# DisplayBoard.net
KiCad netlist of a schematic drawn in EAGLE
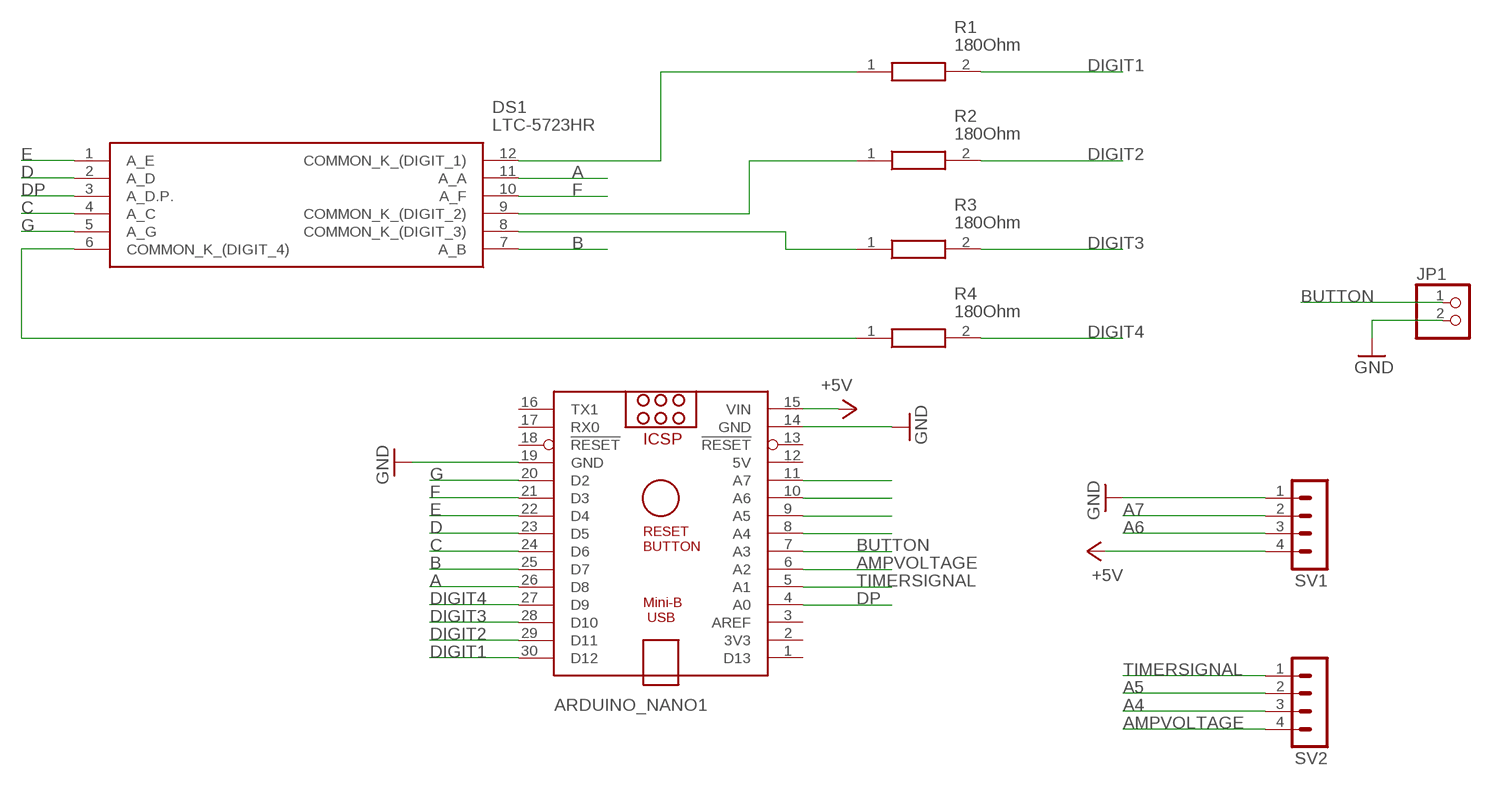
[diagram p0: schematic, sheet 1]

(export (version "E")
  (design (tool "Eeschema 10.0.6"))
  (components
    (comp (ref "ARDUINO_NANO1")
      (value "ARDUINO_NANO")
      (footprint "eagle-import:ARDUINO_NANO")
      (libsource (lib "eagle-import") (part "ARDUINO_NANO"))
    )
    (comp (ref "DS1")
      (value "LTC-5723HR")
      (footprint "eagle-import:DIP1524W75P254L5030H825Q12N")
      (fields (field (name "MOUSER_PART_NUMBER") "859-LTC-5723HR"))
      (libsource (lib "eagle-import") (part "LTC-5723HR"))
    )
    (comp (ref "JP1")
      (value "PINHD-1X2")
      (footprint "eagle-import:1X02")
      (libsource (lib "eagle-import") (part "PINHD-1X2"))
    )
    (comp (ref "R1")
      (value "180Ohm")
      (footprint "eagle-import:RESC2012X60N")
      (fields
        (field (name "MANUFACTURER_PART_NUMBER") "ERA-6AEB181V")
        (field (name "MOUSER_PART_NUMBER") "667-ERA-6AEB181V")
      )
      (libsource (lib "eagle-import") (part "ERA-6AEB181V"))
    )
    (comp (ref "R2")
      (value "180Ohm")
      (footprint "eagle-import:RESC2012X60N")
      (fields
        (field (name "MANUFACTURER_PART_NUMBER") "ERA-6AEB181V")
        (field (name "MOUSER_PART_NUMBER") "667-ERA-6AEB181V")
      )
      (libsource (lib "eagle-import") (part "ERA-6AEB181V"))
    )
    (comp (ref "R3")
      (value "180Ohm")
      (footprint "eagle-import:RESC2012X60N")
      (fields
        (field (name "MANUFACTURER_PART_NUMBER") "ERA-6AEB181V")
        (field (name "MOUSER_PART_NUMBER") "667-ERA-6AEB181V")
      )
      (libsource (lib "eagle-import") (part "ERA-6AEB181V"))
    )
    (comp (ref "R4")
      (value "180Ohm")
      (footprint "eagle-import:RESC2012X60N")
      (fields
        (field (name "MANUFACTURER_PART_NUMBER") "ERA-6AEB181V")
        (field (name "MOUSER_PART_NUMBER") "667-ERA-6AEB181V")
      )
      (libsource (lib "eagle-import") (part "ERA-6AEB181V"))
    )
    (comp (ref "SV1")
      (value "MA04-1")
      (footprint "eagle-import:MA04-1")
      (libsource (lib "eagle-import") (part "MA04-1"))
    )
    (comp (ref "SV2")
      (value "MA04-1")
      (footprint "eagle-import:MA04-1")
      (libsource (lib "eagle-import") (part "MA04-1"))
    )
  )
  (nets
    (net (code "1") (name "+5V") (class "Default")
      (node (ref "ARDUINO_NANO1") (pin "15") (pinfunction "VIN_15") (pintype "power_in"))
      (node (ref "SV1") (pin "4") (pinfunction "4_4") (pintype "passive"))
    )
    (net (code "2") (name "/5V") (class "Default")
      (node (ref "ARDUINO_NANO1") (pin "12") (pinfunction "5V_12") (pintype "power_in"))
    )
    (net (code "3") (name "/A") (class "Default")
      (node (ref "ARDUINO_NANO1") (pin "26") (pinfunction "D8_26") (pintype "bidirectional"))
      (node (ref "DS1") (pin "11") (pinfunction "A_A_11") (pintype "bidirectional"))
    )
    (net (code "4") (name "/A4") (class "Default")
      (node (ref "SV2") (pin "3") (pinfunction "3_3") (pintype "passive"))
    )
    (net (code "5") (name "/A5") (class "Default")
      (node (ref "SV2") (pin "2") (pinfunction "2_2") (pintype "passive"))
    )
    (net (code "6") (name "/A6") (class "Default")
      (node (ref "SV1") (pin "3") (pinfunction "3_3") (pintype "passive"))
    )
    (net (code "7") (name "/A7") (class "Default")
      (node (ref "SV1") (pin "2") (pinfunction "2_2") (pintype "passive"))
    )
    (net (code "8") (name "/AMPVOLTAGE") (class "Default")
      (node (ref "ARDUINO_NANO1") (pin "6") (pinfunction "A2_6") (pintype "bidirectional"))
      (node (ref "SV2") (pin "4") (pinfunction "4_4") (pintype "passive"))
    )
    (net (code "9") (name "/B") (class "Default")
      (node (ref "ARDUINO_NANO1") (pin "25") (pinfunction "D7_25") (pintype "bidirectional"))
      (node (ref "DS1") (pin "7") (pinfunction "A_B_7") (pintype "bidirectional"))
    )
    (net (code "10") (name "/BUTTON") (class "Default")
      (node (ref "ARDUINO_NANO1") (pin "7") (pinfunction "A3_7") (pintype "bidirectional"))
      (node (ref "JP1") (pin "1") (pinfunction "1_1") (pintype "passive"))
    )
    (net (code "11") (name "/C") (class "Default")
      (node (ref "ARDUINO_NANO1") (pin "24") (pinfunction "D6_24") (pintype "bidirectional"))
      (node (ref "DS1") (pin "4") (pinfunction "A_C_4") (pintype "bidirectional"))
    )
    (net (code "12") (name "/D") (class "Default")
      (node (ref "ARDUINO_NANO1") (pin "23") (pinfunction "D5_23") (pintype "bidirectional"))
      (node (ref "DS1") (pin "2") (pinfunction "A_D_2") (pintype "bidirectional"))
    )
    (net (code "13") (name "/DIGIT1") (class "Default")
      (node (ref "ARDUINO_NANO1") (pin "30") (pinfunction "D12_30") (pintype "bidirectional"))
      (node (ref "R1") (pin "2") (pinfunction "2_2") (pintype "bidirectional"))
    )
    (net (code "14") (name "/DIGIT2") (class "Default")
      (node (ref "ARDUINO_NANO1") (pin "29") (pinfunction "D11_29") (pintype "bidirectional"))
      (node (ref "R2") (pin "2") (pinfunction "2_2") (pintype "bidirectional"))
    )
    (net (code "15") (name "/DIGIT3") (class "Default")
      (node (ref "ARDUINO_NANO1") (pin "28") (pinfunction "D10_28") (pintype "bidirectional"))
      (node (ref "R3") (pin "2") (pinfunction "2_2") (pintype "bidirectional"))
    )
    (net (code "16") (name "/DIGIT4") (class "Default")
      (node (ref "ARDUINO_NANO1") (pin "27") (pinfunction "D9_27") (pintype "bidirectional"))
      (node (ref "R4") (pin "2") (pinfunction "2_2") (pintype "bidirectional"))
    )
    (net (code "17") (name "/DP") (class "Default")
      (node (ref "ARDUINO_NANO1") (pin "4") (pinfunction "A0_4") (pintype "bidirectional"))
      (node (ref "DS1") (pin "3") (pinfunction "A_D.P._3") (pintype "bidirectional"))
    )
    (net (code "18") (name "/E") (class "Default")
      (node (ref "ARDUINO_NANO1") (pin "22") (pinfunction "D4_22") (pintype "bidirectional"))
      (node (ref "DS1") (pin "1") (pinfunction "A_E_1") (pintype "bidirectional"))
    )
    (net (code "19") (name "/F") (class "Default")
      (node (ref "ARDUINO_NANO1") (pin "21") (pinfunction "D3_21") (pintype "bidirectional"))
      (node (ref "DS1") (pin "10") (pinfunction "A_F_10") (pintype "bidirectional"))
    )
    (net (code "20") (name "/G") (class "Default")
      (node (ref "ARDUINO_NANO1") (pin "20") (pinfunction "D2_20") (pintype "bidirectional"))
      (node (ref "DS1") (pin "5") (pinfunction "A_G_5") (pintype "bidirectional"))
    )
    (net (code "21") (name "/TIMERSIGNAL") (class "Default")
      (node (ref "ARDUINO_NANO1") (pin "5") (pinfunction "A1_5") (pintype "bidirectional"))
      (node (ref "SV2") (pin "1") (pinfunction "1_1") (pintype "passive"))
    )
    (net (code "22") (name "GND") (class "Default")
      (node (ref "ARDUINO_NANO1") (pin "14") (pinfunction "GND_14") (pintype "power_in"))
      (node (ref "ARDUINO_NANO1") (pin "19") (pinfunction "GND_19") (pintype "power_in"))
      (node (ref "JP1") (pin "2") (pinfunction "2_2") (pintype "passive"))
      (node (ref "SV1") (pin "1") (pinfunction "1_1") (pintype "passive"))
    )
    (net (code "23") (name "Net-(DS1-COMMON_K_(DIGIT_1))") (class "Default")
      (node (ref "DS1") (pin "12") (pinfunction "COMMON_K_(DIGIT_1)_12") (pintype "bidirectional"))
      (node (ref "R1") (pin "1") (pinfunction "1_1") (pintype "bidirectional"))
    )
    (net (code "24") (name "Net-(DS1-COMMON_K_(DIGIT_2))") (class "Default")
      (node (ref "DS1") (pin "9") (pinfunction "COMMON_K_(DIGIT_2)_9") (pintype "bidirectional"))
      (node (ref "R2") (pin "1") (pinfunction "1_1") (pintype "bidirectional"))
    )
    (net (code "25") (name "Net-(DS1-COMMON_K_(DIGIT_3))") (class "Default")
      (node (ref "DS1") (pin "8") (pinfunction "COMMON_K_(DIGIT_3)_8") (pintype "bidirectional"))
      (node (ref "R3") (pin "1") (pinfunction "1_1") (pintype "bidirectional"))
    )
    (net (code "26") (name "Net-(DS1-COMMON_K_(DIGIT_4))") (class "Default")
      (node (ref "DS1") (pin "6") (pinfunction "COMMON_K_(DIGIT_4)_6") (pintype "bidirectional"))
      (node (ref "R4") (pin "1") (pinfunction "1_1") (pintype "bidirectional"))
    )
    (net (code "27") (name "unconnected-(ARDUINO_NANO1-3V3-Pad2)") (class "Default")
      (node (ref "ARDUINO_NANO1") (pin "2") (pinfunction "3V3_2") (pintype "output"))
    )
    (net (code "28") (name "unconnected-(ARDUINO_NANO1-A4-Pad8)") (class "Default")
      (node (ref "ARDUINO_NANO1") (pin "8") (pinfunction "A4_8") (pintype "bidirectional"))
    )
    (net (code "29") (name "unconnected-(ARDUINO_NANO1-A5-Pad9)") (class "Default")
      (node (ref "ARDUINO_NANO1") (pin "9") (pinfunction "A5_9") (pintype "bidirectional"))
    )
    (net (code "30") (name "unconnected-(ARDUINO_NANO1-A6-Pad10)") (class "Default")
      (node (ref "ARDUINO_NANO1") (pin "10") (pinfunction "A6_10") (pintype "bidirectional"))
    )
    (net (code "31") (name "unconnected-(ARDUINO_NANO1-A7-Pad11)") (class "Default")
      (node (ref "ARDUINO_NANO1") (pin "11") (pinfunction "A7_11") (pintype "bidirectional"))
    )
    (net (code "32") (name "unconnected-(ARDUINO_NANO1-AREF-Pad3)") (class "Default")
      (node (ref "ARDUINO_NANO1") (pin "3") (pinfunction "AREF_3") (pintype "input"))
    )
    (net (code "33") (name "unconnected-(ARDUINO_NANO1-D13-Pad1)") (class "Default")
      (node (ref "ARDUINO_NANO1") (pin "1") (pinfunction "D13_1") (pintype "bidirectional"))
    )
    (net (code "34") (name "unconnected-(ARDUINO_NANO1-RX0-Pad17)") (class "Default")
      (node (ref "ARDUINO_NANO1") (pin "17") (pinfunction "RX0_17") (pintype "bidirectional"))
    )
    (net (code "35") (name "unconnected-(ARDUINO_NANO1-TX1-Pad16)") (class "Default")
      (node (ref "ARDUINO_NANO1") (pin "16") (pinfunction "TX1_16") (pintype "bidirectional"))
    )
    (net (code "36") (name "unconnected-(ARDUINO_NANO1-~{RESET}-Pad13)") (class "Default")
      (node (ref "ARDUINO_NANO1") (pin "13") (pinfunction "~{RESET}_13") (pintype "input"))
    )
    (net (code "37") (name "unconnected-(ARDUINO_NANO1-~{RESET}-Pad18)") (class "Default")
      (node (ref "ARDUINO_NANO1") (pin "18") (pinfunction "~{RESET}_18") (pintype "input"))
    )
  )
)
